# pc_healthypi_move_nRF5340_v2.net
KiCad netlist of a schematic drawn in EAGLE
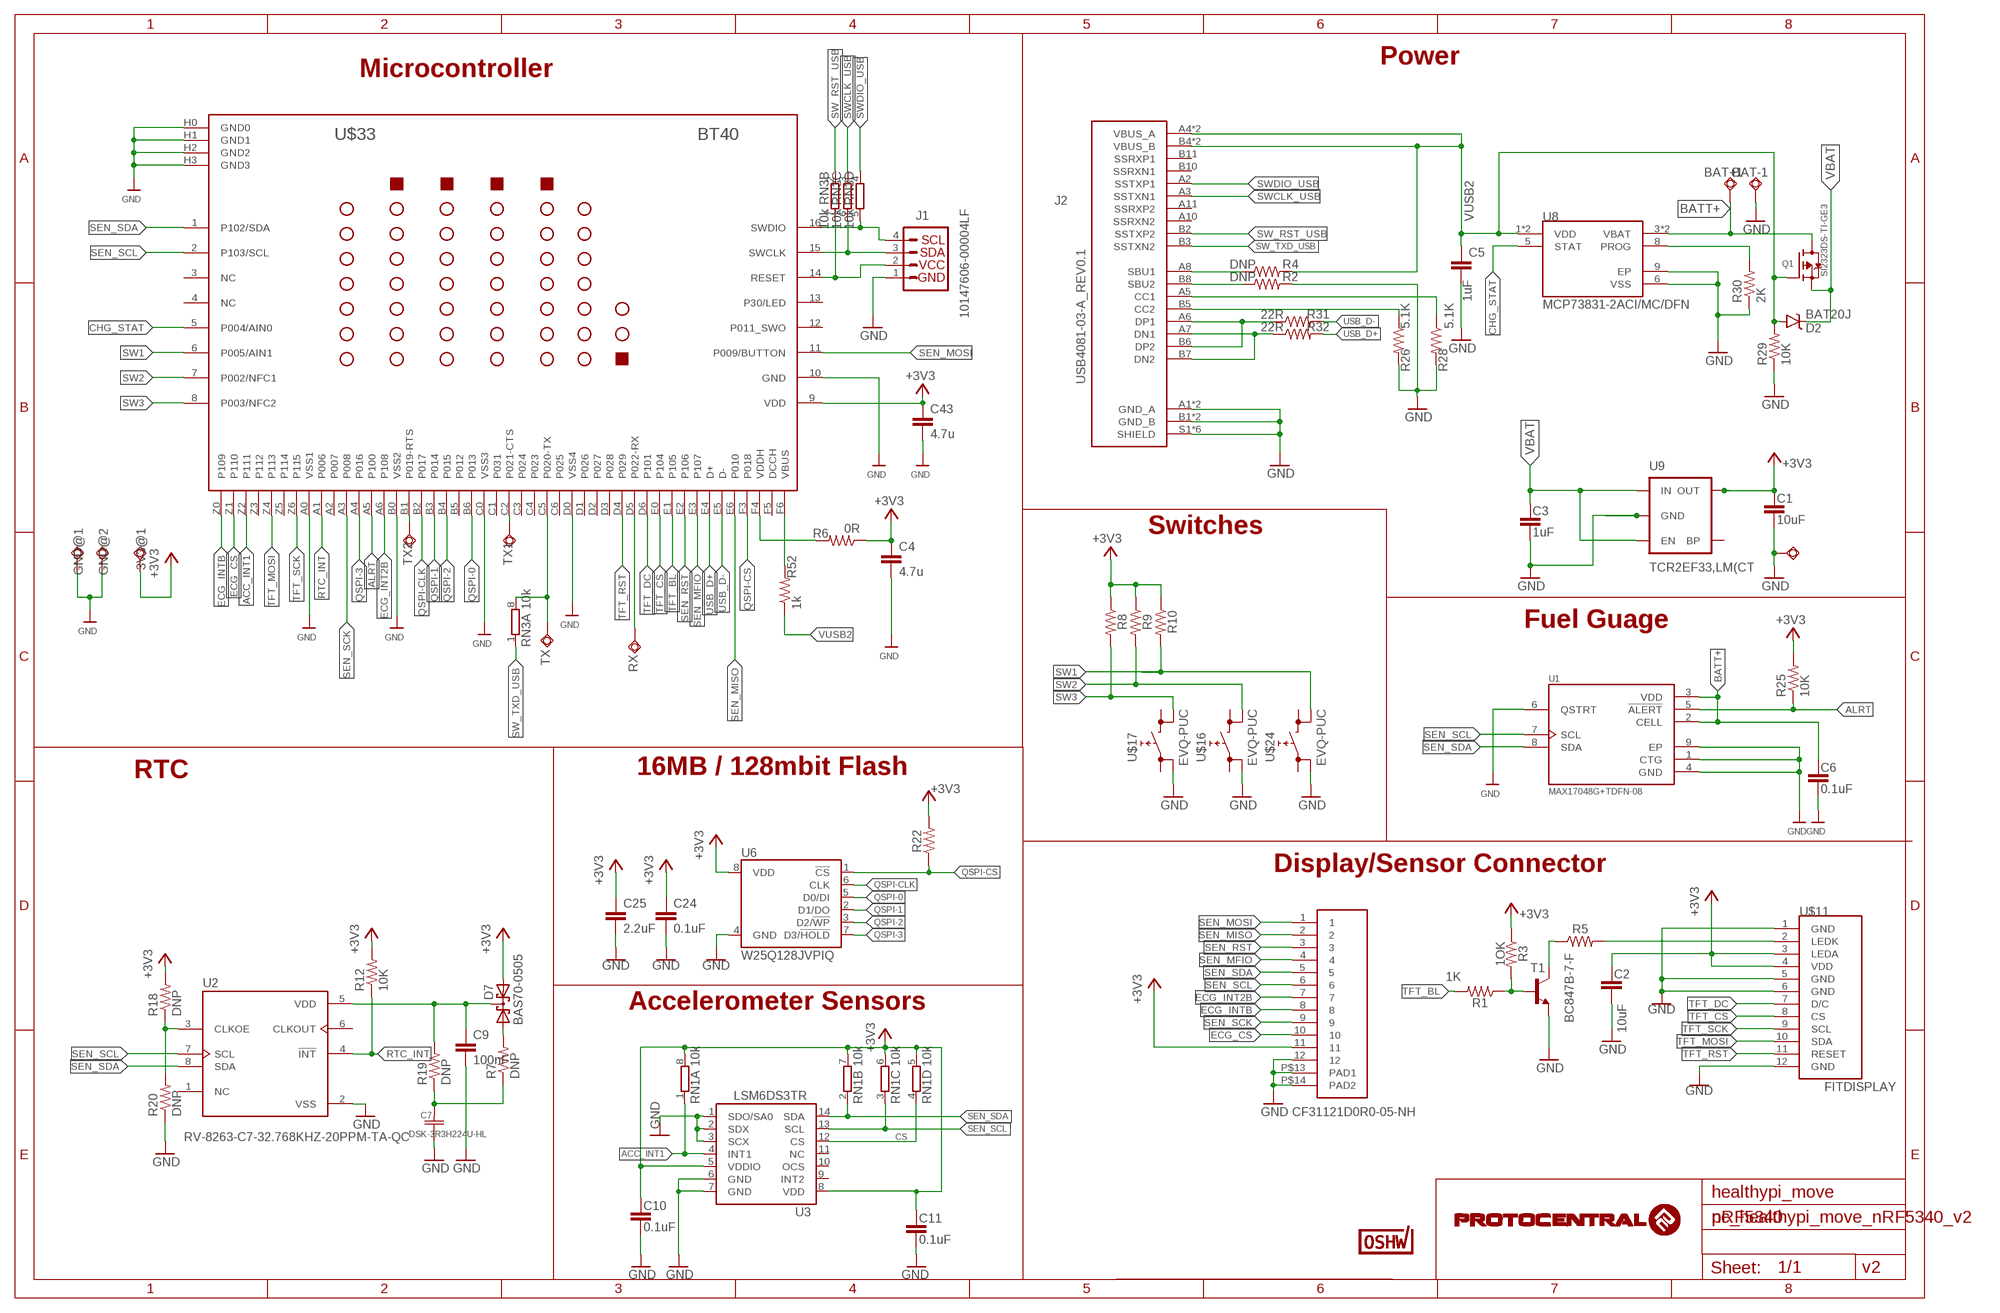
[diagram p0: schematic, sheet 1]

(export (version "E")
  (design (tool "Eeschema 10.0.6"))
  (components
    (comp (ref "3V3@1")
      (value "TPSQTP13SQ")
      (footprint "eagle-import:TP13SQ")
      (libsource (lib "eagle-import") (part "TPSQTP13SQ"))
    )
    (comp (ref "BAT+1")
      (value "TPSQTP13SQ")
      (footprint "eagle-import:TP13SQ")
      (libsource (lib "eagle-import") (part "TPSQTP13SQ"))
    )
    (comp (ref "BAT-1")
      (value "TPSQTP13SQ")
      (footprint "eagle-import:TP13SQ")
      (libsource (lib "eagle-import") (part "TPSQTP13SQ"))
    )
    (comp (ref "C1")
      (value "10uF")
      (footprint "eagle-import:0603@1")
      (libsource (lib "eagle-import") (part "0.1UF-0603-100V-10%"))
    )
    (comp (ref "C2")
      (value "10uF")
      (footprint "eagle-import:0603@1")
      (libsource (lib "eagle-import") (part "0.1UF-0603-100V-10%"))
    )
    (comp (ref "C3")
      (value "1uF")
      (footprint "eagle-import:0402-TIGHT")
      (libsource (lib "eagle-import") (part "0.1UF-0402T-6.3V-10%-X7R"))
    )
    (comp (ref "C4")
      (value "4.7u")
      (footprint "eagle-import:C0402")
      (libsource (lib "eagle-import") (part "C-EUC0402"))
    )
    (comp (ref "C5")
      (value "1uF")
      (footprint "eagle-import:0402-TIGHT")
      (libsource (lib "eagle-import") (part "2.2UF-0402_TIGHT-10V-10%-X5R"))
    )
    (comp (ref "C6")
      (value "0.1uF")
      (footprint "eagle-import:0402-TIGHT")
      (libsource (lib "eagle-import") (part "0.1UF-0402T-6.3V-10%-X7R"))
    )
    (comp (ref "C7")
      (value "DSK-3R3H224U-HL")
      (footprint "eagle-import:CAP_DSK-3R3H224U-HL_ELN")
      (fields (field (name "COPYRIGHT") "Copyright (C) 2023 Ultra Librarian. All rights reserved."))
      (libsource (lib "eagle-import") (part "DSK-3R3H224U-HL"))
    )
    (comp (ref "C9")
      (value "100nF")
      (footprint "eagle-import:C0402")
      (libsource (lib "eagle-import") (part "C-EUC0402"))
    )
    (comp (ref "C10")
      (value "0.1uF")
      (footprint "eagle-import:0402-TIGHT")
      (libsource (lib "eagle-import") (part "0.1UF-0402T-6.3V-10%-X7R"))
    )
    (comp (ref "C11")
      (value "0.1uF")
      (footprint "eagle-import:0402-TIGHT")
      (libsource (lib "eagle-import") (part "0.1UF-0402T-6.3V-10%-X7R"))
    )
    (comp (ref "C24")
      (value "0.1uF")
      (footprint "eagle-import:0402-TIGHT")
      (libsource (lib "eagle-import") (part "0.1UF-0402T-6.3V-10%-X7R"))
    )
    (comp (ref "C25")
      (value "2.2uF")
      (footprint "eagle-import:0402-TIGHT")
      (libsource (lib "eagle-import") (part "2.2UF-0402_TIGHT-10V-10%-X5R"))
    )
    (comp (ref "C43")
      (value "4.7u")
      (footprint "eagle-import:C0402")
      (libsource (lib "eagle-import") (part "C-EUC0402"))
    )
    (comp (ref "D2")
      (value "BAT20J")
      (footprint "eagle-import:SOD-323")
      (libsource (lib "eagle-import") (part "DIODE-SCHOTTKY-BAT20J"))
    )
    (comp (ref "D7")
      (value "BAS70-0505")
      (footprint "eagle-import:SOT23")
      (fields (field (name "MF") "Diotec") (field (name "MP") "BAS70-05"))
      (libsource (lib "eagle-import") (part "BAS70-0505"))
    )
    (comp (ref "GND@1")
      (value "TPSQTP13SQ")
      (footprint "eagle-import:TP13SQ")
      (libsource (lib "eagle-import") (part "TPSQTP13SQ"))
    )
    (comp (ref "GND@2")
      (value "TPSQTP13SQ")
      (footprint "eagle-import:TP13SQ")
      (libsource (lib "eagle-import") (part "TPSQTP13SQ"))
    )
    (comp (ref "J1")
      (value "10147606-00004LF")
      (footprint "eagle-import:JST04_1MM_RA")
      (libsource (lib "eagle-import") (part "QWIIC_CONNECTORJS-1MM"))
    )
    (comp (ref "J2")
      (value "USB4081-03-A_REV0.1")
      (footprint "eagle-import:GCT_USB4081-03-A_REV0.1")
      (fields (field (name "MF") "Global Connector Technology") (field (name "MP") "USB4081-03-A"))
      (libsource (lib "eagle-import") (part "USB4081-03-A_REV0.1"))
    )
    (comp (ref "Q1")
      (value "SI2323DS-TI-GE3")
      (footprint "eagle-import:SOT23-R")
      (libsource (lib "eagle-import") (part "MOSFET-P"))
    )
    (comp (ref "R1")
      (value "200")
      (footprint "eagle-import:R0402")
      (libsource (lib "eagle-import") (part "R-US_R0402"))
    )
    (comp (ref "R2")
      (value "DNP")
      (footprint "eagle-import:0402-RES")
      (libsource (lib "eagle-import") (part "RESISTOR0402-RES"))
    )
    (comp (ref "R3")
      (value "200")
      (footprint "eagle-import:R0402")
      (libsource (lib "eagle-import") (part "R-US_R0402"))
    )
    (comp (ref "R4")
      (value "DNP")
      (footprint "eagle-import:0402-RES")
      (libsource (lib "eagle-import") (part "RESISTOR0402-RES"))
    )
    (comp (ref "R5")
      (value "200R")
      (footprint "eagle-import:R0402")
      (libsource (lib "eagle-import") (part "R-US_R0402"))
    )
    (comp (ref "R6")
      (value "0R")
      (footprint "eagle-import:0402-RES")
      (libsource (lib "eagle-import") (part "RESISTOR0402-RES"))
    )
    (comp (ref "R7")
      (value "DNP")
      (footprint "eagle-import:R0402")
      (libsource (lib "eagle-import") (part "R-US_R0402"))
    )
    (comp (ref "R8")
      (value "200")
      (footprint "eagle-import:R0402")
      (libsource (lib "eagle-import") (part "R-US_R0402"))
    )
    (comp (ref "R9")
      (value "200")
      (footprint "eagle-import:R0402")
      (libsource (lib "eagle-import") (part "R-US_R0402"))
    )
    (comp (ref "R10")
      (value "200")
      (footprint "eagle-import:R0402")
      (libsource (lib "eagle-import") (part "R-US_R0402"))
    )
    (comp (ref "R12")
      (value "10K")
      (footprint "eagle-import:R0402")
      (libsource (lib "eagle-import") (part "R-US_R0402"))
    )
    (comp (ref "R18")
      (value "DNP")
      (footprint "eagle-import:R0402")
      (libsource (lib "eagle-import") (part "R-US_R0402"))
    )
    (comp (ref "R19")
      (value "DNP")
      (footprint "eagle-import:R0402")
      (libsource (lib "eagle-import") (part "R-US_R0402"))
    )
    (comp (ref "R20")
      (value "DNP")
      (footprint "eagle-import:R0402")
      (libsource (lib "eagle-import") (part "R-US_R0402"))
    )
    (comp (ref "R22")
      (value "10k")
      (footprint "eagle-import:R0402")
      (libsource (lib "eagle-import") (part "R-US_R0402"))
    )
    (comp (ref "R25")
      (value "10K")
      (footprint "eagle-import:0402-RES")
      (libsource (lib "eagle-import") (part "RESISTOR0402-RES"))
    )
    (comp (ref "R26")
      (value "5.1K")
      (footprint "eagle-import:0402-RES")
      (libsource (lib "eagle-import") (part "RESISTOR0402-RES"))
    )
    (comp (ref "R28")
      (value "5.1K")
      (footprint "eagle-import:0402-RES")
      (libsource (lib "eagle-import") (part "RESISTOR0402-RES"))
    )
    (comp (ref "R29")
      (value "10K")
      (footprint "eagle-import:R0402")
      (libsource (lib "eagle-import") (part "R-US_R0402"))
    )
    (comp (ref "R30")
      (value "2K")
      (footprint "eagle-import:R0402")
      (libsource (lib "eagle-import") (part "R-US_R0402"))
    )
    (comp (ref "R31")
      (value "22R")
      (footprint "eagle-import:0402-RES")
      (libsource (lib "eagle-import") (part "RESISTOR0402-RES"))
    )
    (comp (ref "R32")
      (value "22R")
      (footprint "eagle-import:0402-RES")
      (libsource (lib "eagle-import") (part "RESISTOR0402-RES"))
    )
    (comp (ref "R52")
      (value "1k")
      (footprint "eagle-import:0402-RES")
      (libsource (lib "eagle-import") (part "RESISTOR0402-RES"))
    )
    (comp (ref "RN1")
      (value "10k")
      (footprint "eagle-import:4X0402ARV341")
      (libsource (lib "eagle-import") (part "4R-N0402ARV341"))
    )
    (comp (ref "RN3")
      (value "10k")
      (footprint "eagle-import:4X0402ARV341")
      (libsource (lib "eagle-import") (part "4R-N0402ARV341"))
    )
    (comp (ref "RX")
      (value "TPSQTP13SQ")
      (footprint "eagle-import:TP13SQ")
      (libsource (lib "eagle-import") (part "TPSQTP13SQ"))
    )
    (comp (ref "SWIO6")
      (value "TPSQTP11R")
      (footprint "eagle-import:TP11R")
      (libsource (lib "eagle-import") (part "TPSQTP11R"))
    )
    (comp (ref "T1")
      (value "BC847B-7-F")
      (footprint "eagle-import:SOT23-BEC")
      (libsource (lib "eagle-import") (part "-NPN-SOT23-BECMMBT2222ALT1"))
    )
    (comp (ref "TX")
      (value "TPSQTP13SQ")
      (footprint "eagle-import:TP13SQ")
      (libsource (lib "eagle-import") (part "TPSQTP13SQ"))
    )
    (comp (ref "TX1")
      (value "TPSQTP13SQ")
      (footprint "eagle-import:TP13SQ")
      (libsource (lib "eagle-import") (part "TPSQTP13SQ"))
    )
    (comp (ref "TX2")
      (value "TPSQTP13SQ")
      (footprint "eagle-import:TP13SQ")
      (libsource (lib "eagle-import") (part "TPSQTP13SQ"))
    )
    (comp (ref "U$5")
      (value "CF31121D0R0-05-NH")
      (footprint "eagle-import:CF31121D0R0-05-NH")
      (libsource (lib "eagle-import") (part "CF31121D0R0-05-NH"))
    )
    (comp (ref "U$9")
      (value "CERT-SMALL")
      (footprint "eagle-import:CERT-SMALL-SILK")
      (libsource (lib "eagle-import") (part "CERT-SMALL"))
    )
    (comp (ref "U$11")
      (value "FITDISPLAY")
      (footprint "eagle-import:FITDISPLAY")
      (libsource (lib "eagle-import") (part "FITDISPLAY"))
    )
    (comp (ref "U$16")
      (value "EVQ-PUC")
      (footprint "eagle-import:EVQ-PUC")
      (libsource (lib "eagle-import") (part "EVQ-PUC"))
    )
    (comp (ref "U$17")
      (value "EVQ-PUC")
      (footprint "eagle-import:EVQ-PUC")
      (libsource (lib "eagle-import") (part "EVQ-PUC"))
    )
    (comp (ref "U$24")
      (value "EVQ-PUC")
      (footprint "eagle-import:EVQ-PUC")
      (libsource (lib "eagle-import") (part "EVQ-PUC"))
    )
    (comp (ref "U$33")
      (value "BT40")
      (footprint "eagle-import:BT40")
      (libsource (lib "eagle-import") (part "BT40"))
    )
    (comp (ref "U1")
      (value "MAX17048G+TDFN-08")
      (footprint "eagle-import:SON50P200X200X80-9N")
      (fields (field (name "MF") "Analog Devices") (field (name "MP") "MAX17048G+"))
      (libsource (lib "eagle-import") (part "MAX17048G+TDFN-08"))
    )
    (comp (ref "U2")
      (value "RV-8263-C7-32.768KHZ-20PPM-TA-QC")
      (footprint "eagle-import:IC_RV-8263-C7-32.768KHZ-20PPM-TA-QC")
      (fields (field (name "MF") "Micro Crystal"))
      (libsource (lib "eagle-import") (part "RV-8263-C7-32.768KHZ-20PPM-TA-QC"))
    )
    (comp (ref "U3")
      (value "LSM6DS3TR")
      (footprint "eagle-import:LGA14L")
      (libsource (lib "eagle-import") (part "LSM6DS3"))
    )
    (comp (ref "U6")
      (value "W25Q128JVPIQ")
      (footprint "eagle-import:WSON-8-6X5-SKINNY_CENTERPAD")
      (libsource (lib "eagle-import") (part "W25QXX128MBIT-6X5-SKINNY_CENTER"))
    )
    (comp (ref "U8")
      (value "MCP73831-2ACI/MC/DFN")
      (footprint "eagle-import:SON50P200X300X100-9N")
      (fields (field (name "MF") "Microchip Technology") (field (name "MP") "MCP73831-2ACI/MC"))
      (libsource (lib "eagle-import") (part "MCP73831-2ACI/MC/DFN"))
    )
    (comp (ref "U9")
      (value "TCR2EF33,LM(CT")
      (footprint "eagle-import:SOT23-5")
      (libsource (lib "eagle-import") (part "V_REG_LDOSMD"))
    )
  )
  (nets
    (net (code "1") (name "+3V3") (class "Default")
      (node (ref "3V3@1") (pin "TP") (pinfunction "TP_TP") (pintype "input"))
      (node (ref "C1") (pin "1") (pinfunction "1_1") (pintype "passive"))
      (node (ref "C10") (pin "1") (pinfunction "1_1") (pintype "passive"))
      (node (ref "C11") (pin "1") (pinfunction "1_1") (pintype "passive"))
      (node (ref "C2") (pin "1") (pinfunction "1_1") (pintype "passive"))
      (node (ref "C24") (pin "1") (pinfunction "1_1") (pintype "passive"))
      (node (ref "C25") (pin "1") (pinfunction "1_1") (pintype "passive"))
      (node (ref "C4") (pin "1") (pinfunction "1_1") (pintype "passive"))
      (node (ref "C43") (pin "1") (pinfunction "1_1") (pintype "passive"))
      (node (ref "D7") (pin "2") (pinfunction "A2_2") (pintype "passive"))
      (node (ref "R10") (pin "1") (pinfunction "1_1") (pintype "passive"))
      (node (ref "R12") (pin "2") (pinfunction "2_2") (pintype "passive"))
      (node (ref "R18") (pin "2") (pinfunction "2_2") (pintype "passive"))
      (node (ref "R22") (pin "2") (pinfunction "2_2") (pintype "passive"))
      (node (ref "R25") (pin "2") (pinfunction "2_2") (pintype "passive"))
      (node (ref "R3") (pin "1") (pinfunction "1_1") (pintype "passive"))
      (node (ref "R6") (pin "1") (pinfunction "1_1") (pintype "passive"))
      (node (ref "R8") (pin "1") (pinfunction "1_1") (pintype "passive"))
      (node (ref "R9") (pin "1") (pinfunction "1_1") (pintype "passive"))
      (node (ref "RN1") (pin "5") (pinfunction "2_5") (pintype "passive"))
      (node (ref "RN1") (pin "6") (pinfunction "2_6") (pintype "passive"))
      (node (ref "RN1") (pin "7") (pinfunction "2_7") (pintype "passive"))
      (node (ref "RN1") (pin "8") (pinfunction "2_8") (pintype "passive"))
      (node (ref "U$11") (pin "3") (pinfunction "LEDA_3") (pintype "bidirectional"))
      (node (ref "U$11") (pin "4") (pinfunction "VDD_4") (pintype "bidirectional"))
      (node (ref "U$33") (pin "9") (pinfunction "VDD_9") (pintype "bidirectional"))
      (node (ref "U$5") (pin "11") (pinfunction "11_11") (pintype "bidirectional"))
      (node (ref "U3") (pin "5") (pinfunction "VDDIO_5") (pintype "bidirectional"))
      (node (ref "U3") (pin "8") (pinfunction "VDD_8") (pintype "bidirectional"))
      (node (ref "U6") (pin "8") (pinfunction "VDD_8") (pintype "bidirectional"))
      (node (ref "U9") (pin "5") (pinfunction "OUT_5") (pintype "passive"))
    )
    (net (code "2") (name "/CS") (class "Default")
      (node (ref "RN1") (pin "4") (pinfunction "1_4") (pintype "passive"))
      (node (ref "U3") (pin "12") (pinfunction "CS_12") (pintype "bidirectional"))
    )
    (net (code "3") (name "ACC_INT1") (class "Default")
      (node (ref "RN1") (pin "1") (pinfunction "1_1") (pintype "passive"))
      (node (ref "U$33") (pin "Z2") (pinfunction "P111_Z2") (pintype "bidirectional"))
      (node (ref "U3") (pin "4") (pinfunction "INT1_4") (pintype "bidirectional"))
    )
    (net (code "4") (name "ALRT") (class "Default")
      (node (ref "R25") (pin "1") (pinfunction "1_1") (pintype "passive"))
      (node (ref "U$33") (pin "A5") (pinfunction "P100_A5") (pintype "bidirectional"))
      (node (ref "U1") (pin "5") (pinfunction "~{ALERT}_5") (pintype "output"))
    )
    (net (code "5") (name "BATT+") (class "Default")
      (node (ref "BAT+1") (pin "TP") (pinfunction "TP_TP") (pintype "input"))
      (node (ref "C6") (pin "1") (pinfunction "1_1") (pintype "passive"))
      (node (ref "Q1") (pin "3") (pinfunction "D_3") (pintype "passive"))
      (node (ref "U1") (pin "2") (pinfunction "CELL_2") (pintype "power_in"))
      (node (ref "U1") (pin "3") (pinfunction "VDD_3") (pintype "power_in"))
      (node (ref "U8") (pin "3") (pinfunction "VBAT_3") (pintype "output"))
      (node (ref "U8") (pin "4") (pinfunction "VBAT_4") (pintype "output"))
    )
    (net (code "6") (name "CHG_STAT") (class "Default")
      (node (ref "U$33") (pin "5") (pinfunction "P004/AIN0_5") (pintype "bidirectional"))
      (node (ref "U8") (pin "5") (pinfunction "STAT_5") (pintype "output"))
    )
    (net (code "7") (name "ECG_CS") (class "Default")
      (node (ref "U$33") (pin "Z1") (pinfunction "P110_Z1") (pintype "bidirectional"))
      (node (ref "U$5") (pin "10") (pinfunction "10_10") (pintype "bidirectional"))
    )
    (net (code "8") (name "ECG_INT2B") (class "Default")
      (node (ref "U$33") (pin "A6") (pinfunction "P108_A6") (pintype "bidirectional"))
      (node (ref "U$5") (pin "7") (pinfunction "7_7") (pintype "bidirectional"))
    )
    (net (code "9") (name "ECG_INTB") (class "Default")
      (node (ref "U$33") (pin "Z0") (pinfunction "P109_Z0") (pintype "bidirectional"))
      (node (ref "U$5") (pin "8") (pinfunction "8_8") (pintype "bidirectional"))
    )
    (net (code "10") (name "GND") (class "Default")
      (node (ref "BAT-1") (pin "TP") (pinfunction "TP_TP") (pintype "input"))
      (node (ref "C1") (pin "2") (pinfunction "2_2") (pintype "passive"))
      (node (ref "C10") (pin "2") (pinfunction "2_2") (pintype "passive"))
      (node (ref "C11") (pin "2") (pinfunction "2_2") (pintype "passive"))
      (node (ref "C2") (pin "2") (pinfunction "2_2") (pintype "passive"))
      (node (ref "C24") (pin "2") (pinfunction "2_2") (pintype "passive"))
      (node (ref "C25") (pin "2") (pinfunction "2_2") (pintype "passive"))
      (node (ref "C3") (pin "2") (pinfunction "2_2") (pintype "passive"))
      (node (ref "C4") (pin "2") (pinfunction "2_2") (pintype "passive"))
      (node (ref "C43") (pin "2") (pinfunction "2_2") (pintype "passive"))
      (node (ref "C5") (pin "2") (pinfunction "2_2") (pintype "passive"))
      (node (ref "C6") (pin "2") (pinfunction "2_2") (pintype "passive"))
      (node (ref "C7") (pin "1") (pinfunction "1_1") (pintype "passive"))
      (node (ref "C9") (pin "2") (pinfunction "2_2") (pintype "passive"))
      (node (ref "GND@1") (pin "TP") (pinfunction "TP_TP") (pintype "input"))
      (node (ref "GND@2") (pin "TP") (pinfunction "TP_TP") (pintype "input"))
      (node (ref "J1") (pin "1") (pinfunction "1_1") (pintype "power_in"))
      (node (ref "J2") (pin "A1") (pinfunction "GND_A_A1") (pintype "power_in"))
      (node (ref "J2") (pin "A12") (pinfunction "GND_A_A12") (pintype "power_in"))
      (node (ref "J2") (pin "B1") (pinfunction "GND_B_B1") (pintype "power_in"))
      (node (ref "J2") (pin "B12") (pinfunction "GND_B_B12") (pintype "power_in"))
      (node (ref "J2") (pin "S1") (pinfunction "SHIELD_S1") (pintype "passive"))
      (node (ref "J2") (pin "S2") (pinfunction "SHIELD_S2") (pintype "passive"))
      (node (ref "J2") (pin "S3") (pinfunction "SHIELD_S3") (pintype "passive"))
      (node (ref "J2") (pin "S4") (pinfunction "SHIELD_S4") (pintype "passive"))
      (node (ref "J2") (pin "S5") (pinfunction "SHIELD_S5") (pintype "passive"))
      (node (ref "J2") (pin "S6") (pinfunction "SHIELD_S6") (pintype "passive"))
      (node (ref "R2") (pin "2") (pinfunction "2_2") (pintype "passive"))
      (node (ref "R20") (pin "1") (pinfunction "1_1") (pintype "passive"))
      (node (ref "R26") (pin "2") (pinfunction "2_2") (pintype "passive"))
      (node (ref "R28") (pin "2") (pinfunction "2_2") (pintype "passive"))
      (node (ref "R29") (pin "1") (pinfunction "1_1") (pintype "passive"))
      (node (ref "R30") (pin "1") (pinfunction "1_1") (pintype "passive"))
      (node (ref "SWIO6") (pin "TP") (pinfunction "TP_TP") (pintype "input"))
      (node (ref "T1") (pin "E") (pinfunction "E_E") (pintype "passive"))
      (node (ref "U$11") (pin "1") (pinfunction "GND_1") (pintype "bidirectional"))
      (node (ref "U$11") (pin "12") (pinfunction "GND_12") (pintype "bidirectional"))
      (node (ref "U$11") (pin "5") (pinfunction "GND_5") (pintype "bidirectional"))
      (node (ref "U$11") (pin "6") (pinfunction "GND_6") (pintype "bidirectional"))
      (node (ref "U$16") (pin "3") (pinfunction "0_3") (pintype "passive"))
      (node (ref "U$17") (pin "3") (pinfunction "0_3") (pintype "passive"))
      (node (ref "U$24") (pin "3") (pinfunction "0_3") (pintype "passive"))
      (node (ref "U$33") (pin "10") (pinfunction "GND_10") (pintype "bidirectional"))
      (node (ref "U$33") (pin "A0") (pinfunction "VSS1_A0") (pintype "bidirectional"))
      (node (ref "U$33") (pin "B0") (pinfunction "VSS2_B0") (pintype "bidirectional"))
      (node (ref "U$33") (pin "C0") (pinfunction "VSS3_C0") (pintype "bidirectional"))
      (node (ref "U$33") (pin "D0") (pinfunction "VSS4_D0") (pintype "bidirectional"))
      (node (ref "U$33") (pin "H0") (pinfunction "GND0_H0") (pintype "bidirectional"))
      (node (ref "U$33") (pin "H1") (pinfunction "GND1_H1") (pintype "bidirectional"))
      (node (ref "U$33") (pin "H2") (pinfunction "GND2_H2") (pintype "bidirectional"))
      (node (ref "U$33") (pin "H3") (pinfunction "GND3_H3") (pintype "bidirectional"))
      (node (ref "U$5") (pin "12") (pinfunction "12_12") (pintype "bidirectional"))
      (node (ref "U$5") (pin "P$13") (pinfunction "PAD1_P$13") (pintype "bidirectional"))
      (node (ref "U$5") (pin "P$14") (pinfunction "PAD2_P$14") (pintype "bidirectional"))
      (node (ref "U1") (pin "1") (pinfunction "CTG_1") (pintype "power_in"))
      (node (ref "U1") (pin "4") (pinfunction "GND_4") (pintype "power_in"))
      (node (ref "U1") (pin "6") (pinfunction "QSTRT_6") (pintype "input"))
      (node (ref "U1") (pin "9") (pinfunction "EP_9") (pintype "power_in"))
      (node (ref "U2") (pin "2") (pinfunction "VSS_2") (pintype "power_in"))
      (node (ref "U3") (pin "1") (pinfunction "SDO/SA0_1") (pintype "bidirectional"))
      (node (ref "U3") (pin "2") (pinfunction "SDX_2") (pintype "bidirectional"))
      (node (ref "U3") (pin "3") (pinfunction "SCX_3") (pintype "bidirectional"))
      (node (ref "U3") (pin "6") (pinfunction "GND_6") (pintype "bidirectional"))
      (node (ref "U3") (pin "7") (pinfunction "GND_7") (pintype "bidirectional"))
      (node (ref "U6") (pin "4") (pinfunction "GND_4") (pintype "bidirectional"))
      (node (ref "U8") (pin "6") (pinfunction "VSS_6") (pintype "power_in"))
      (node (ref "U8") (pin "9") (pinfunction "EP_9") (pintype "power_in"))
      (node (ref "U9") (pin "2") (pinfunction "GND_2") (pintype "input"))
    )
    (net (code "11") (name "Net-(C7-Pad2)") (class "Default")
      (node (ref "C7") (pin "2") (pinfunction "2_2") (pintype "passive"))
      (node (ref "R19") (pin "1") (pinfunction "1_1") (pintype "passive"))
      (node (ref "R7") (pin "1") (pinfunction "1_1") (pintype "passive"))
    )
    (net (code "12") (name "Net-(D7-A1)") (class "Default")
      (node (ref "D7") (pin "1") (pinfunction "A1_1") (pintype "passive"))
      (node (ref "R7") (pin "2") (pinfunction "2_2") (pintype "passive"))
    )
    (net (code "13") (name "Net-(D7-K1K2)") (class "Default")
      (node (ref "C9") (pin "1") (pinfunction "1_1") (pintype "passive"))
      (node (ref "D7") (pin "3") (pinfunction "K1K2_3") (pintype "passive"))
      (node (ref "R19") (pin "2") (pinfunction "2_2") (pintype "passive"))
      (node (ref "U2") (pin "5") (pinfunction "VDD_5") (pintype "power_in"))
    )
    (net (code "14") (name "Net-(J2-CC1)") (class "Default")
      (node (ref "J2") (pin "A5") (pinfunction "CC1_A5") (pintype "bidirectional"))
      (node (ref "R28") (pin "1") (pinfunction "1_1") (pintype "passive"))
    )
    (net (code "15") (name "Net-(J2-CC2)") (class "Default")
      (node (ref "J2") (pin "B5") (pinfunction "CC2_B5") (pintype "bidirectional"))
      (node (ref "R26") (pin "1") (pinfunction "1_1") (pintype "passive"))
    )
    (net (code "16") (name "Net-(J2-DN1)") (class "Default")
      (node (ref "J2") (pin "A7") (pinfunction "DN1_A7") (pintype "bidirectional"))
      (node (ref "J2") (pin "B7") (pinfunction "DN2_B7") (pintype "bidirectional"))
      (node (ref "R32") (pin "1") (pinfunction "1_1") (pintype "passive"))
    )
    (net (code "17") (name "Net-(J2-DP1)") (class "Default")
      (node (ref "J2") (pin "A6") (pinfunction "DP1_A6") (pintype "bidirectional"))
      (node (ref "J2") (pin "B6") (pinfunction "DP2_B6") (pintype "bidirectional"))
      (node (ref "R31") (pin "1") (pinfunction "1_1") (pintype "passive"))
    )
    (net (code "18") (name "Net-(J2-SBU1)") (class "Default")
      (node (ref "J2") (pin "A8") (pinfunction "SBU1_A8") (pintype "bidirectional"))
      (node (ref "R4") (pin "1") (pinfunction "1_1") (pintype "passive"))
    )
    (net (code "19") (name "Net-(J2-SBU2)") (class "Default")
      (node (ref "J2") (pin "B8") (pinfunction "SBU2_B8") (pintype "bidirectional"))
      (node (ref "R2") (pin "1") (pinfunction "1_1") (pintype "passive"))
    )
    (net (code "20") (name "Net-(R1-Pad1)") (class "Default")
      (node (ref "R1") (pin "1") (pinfunction "1_1") (pintype "passive"))
      (node (ref "R3") (pin "2") (pinfunction "2_2") (pintype "passive"))
      (node (ref "T1") (pin "B") (pinfunction "B_B") (pintype "passive"))
    )
    (net (code "21") (name "Net-(R5-Pad1)") (class "Default")
      (node (ref "R5") (pin "1") (pinfunction "1_1") (pintype "passive"))
      (node (ref "T1") (pin "C") (pinfunction "C_C") (pintype "passive"))
    )
    (net (code "22") (name "Net-(RN3A-2)") (class "Default")
      (node (ref "RN3") (pin "8") (pinfunction "2_8") (pintype "passive"))
      (node (ref "TX") (pin "TP") (pinfunction "TP_TP") (pintype "input"))
      (node (ref "U$33") (pin "C5") (pinfunction "P020-TX_C5") (pintype "bidirectional"))
    )
    (net (code "23") (name "Net-(RN3B-2)") (class "Default")
      (node (ref "J1") (pin "2") (pinfunction "2_2") (pintype "power_in"))
      (node (ref "RN3") (pin "7") (pinfunction "2_7") (pintype "passive"))
      (node (ref "U$33") (pin "14") (pinfunction "RESET_14") (pintype "bidirectional"))
    )
    (net (code "24") (name "Net-(RN3C-2)") (class "Default")
      (node (ref "J1") (pin "3") (pinfunction "3_3") (pintype "passive"))
      (node (ref "RN3") (pin "6") (pinfunction "2_6") (pintype "passive"))
      (node (ref "U$33") (pin "15") (pinfunction "SWCLK_15") (pintype "bidirectional"))
    )
    (net (code "25") (name "Net-(RN3D-2)") (class "Default")
      (node (ref "J1") (pin "4") (pinfunction "4_4") (pintype "passive"))
      (node (ref "RN3") (pin "5") (pinfunction "2_5") (pintype "passive"))
      (node (ref "U$33") (pin "16") (pinfunction "SWDIO_16") (pintype "bidirectional"))
    )
    (net (code "26") (name "Net-(U$11-LEDK)") (class "Default")
      (node (ref "R5") (pin "2") (pinfunction "2_2") (pintype "passive"))
      (node (ref "U$11") (pin "2") (pinfunction "LEDK_2") (pintype "bidirectional"))
    )
    (net (code "27") (name "Net-(U$33-P019-RTS)") (class "Default")
      (node (ref "TX2") (pin "TP") (pinfunction "TP_TP") (pintype "input"))
      (node (ref "U$33") (pin "B1") (pinfunction "P019-RTS_B1") (pintype "bidirectional"))
    )
    (net (code "28") (name "Net-(U$33-P021-CTS)") (class "Default")
      (node (ref "TX1") (pin "TP") (pinfunction "TP_TP") (pintype "input"))
      (node (ref "U$33") (pin "C2") (pinfunction "P021-CTS_C2") (pintype "bidirectional"))
    )
    (net (code "29") (name "Net-(U$33-P022-RX)") (class "Default")
      (node (ref "RX") (pin "TP") (pinfunction "TP_TP") (pintype "input"))
      (node (ref "U$33") (pin "D5") (pinfunction "P022-RX_D5") (pintype "bidirectional"))
    )
    (net (code "30") (name "Net-(U$33-VBUS)") (class "Default")
      (node (ref "R52") (pin "2") (pinfunction "2_2") (pintype "passive"))
      (node (ref "U$33") (pin "F6") (pinfunction "VBUS_F6") (pintype "bidirectional"))
    )
    (net (code "31") (name "Net-(U$33-VDDH)") (class "Default")
      (node (ref "R6") (pin "2") (pinfunction "2_2") (pintype "passive"))
      (node (ref "U$33") (pin "F4") (pinfunction "VDDH_F4") (pintype "bidirectional"))
    )
    (net (code "32") (name "Net-(U2-CLKOE)") (class "Default")
      (node (ref "R18") (pin "1") (pinfunction "1_1") (pintype "passive"))
      (node (ref "R20") (pin "2") (pinfunction "2_2") (pintype "passive"))
      (node (ref "U2") (pin "3") (pinfunction "CLKOE_3") (pintype "input"))
    )
    (net (code "33") (name "Net-(U8-PROG)") (class "Default")
      (node (ref "R30") (pin "2") (pinfunction "2_2") (pintype "passive"))
      (node (ref "U8") (pin "8") (pinfunction "PROG_8") (pintype "input"))
    )
    (net (code "34") (name "QSPI-0") (class "Default")
      (node (ref "U$33") (pin "B6") (pinfunction "P013_B6") (pintype "bidirectional"))
      (node (ref "U6") (pin "5") (pinfunction "D0/DI_5") (pintype "bidirectional"))
    )
    (net (code "35") (name "QSPI-1") (class "Default")
      (node (ref "U$33") (pin "B3") (pinfunction "P014_B3") (pintype "bidirectional"))
      (node (ref "U6") (pin "2") (pinfunction "D1/DO_2") (pintype "bidirectional"))
    )
    (net (code "36") (name "QSPI-2") (class "Default")
      (node (ref "U$33") (pin "B4") (pinfunction "P015_B4") (pintype "bidirectional"))
      (node (ref "U6") (pin "3") (pinfunction "D2/~{WP}_3") (pintype "bidirectional"))
    )
    (net (code "37") (name "QSPI-3") (class "Default")
      (node (ref "U$33") (pin "A4") (pinfunction "P016_A4") (pintype "bidirectional"))
      (node (ref "U6") (pin "7") (pinfunction "D3/~{HOLD}_7") (pintype "bidirectional"))
    )
    (net (code "38") (name "QSPI-CLK") (class "Default")
      (node (ref "U$33") (pin "B2") (pinfunction "P017_B2") (pintype "bidirectional"))
      (node (ref "U6") (pin "6") (pinfunction "CLK_6") (pintype "bidirectional"))
    )
    (net (code "39") (name "QSPI-CS") (class "Default")
      (node (ref "R22") (pin "1") (pinfunction "1_1") (pintype "passive"))
      (node (ref "U$33") (pin "F3") (pinfunction "P018_F3") (pintype "bidirectional"))
      (node (ref "U6") (pin "1") (pinfunction "~{CS}_1") (pintype "bidirectional"))
    )
    (net (code "40") (name "RTC_INT") (class "Default")
      (node (ref "R12") (pin "1") (pinfunction "1_1") (pintype "passive"))
      (node (ref "U$33") (pin "A1") (pinfunction "P006_A1") (pintype "bidirectional"))
      (node (ref "U2") (pin "4") (pinfunction "~{INT}_4") (pintype "output"))
    )
    (net (code "41") (name "SEN_MFIO") (class "Default")
      (node (ref "U$33") (pin "E3") (pinfunction "P107_E3") (pintype "bidirectional"))
      (node (ref "U$5") (pin "4") (pinfunction "4_4") (pintype "bidirectional"))
    )
    (net (code "42") (name "SEN_MISO") (class "Default")
      (node (ref "U$33") (pin "E6") (pinfunction "P010_E6") (pintype "bidirectional"))
      (node (ref "U$5") (pin "2") (pinfunction "2_2") (pintype "bidirectional"))
    )
    (net (code "43") (name "SEN_MOSI") (class "Default")
      (node (ref "U$33") (pin "11") (pinfunction "P009/BUTTON_11") (pintype "bidirectional"))
      (node (ref "U$5") (pin "1") (pinfunction "1_1") (pintype "bidirectional"))
    )
    (net (code "44") (name "SEN_RST") (class "Default")
      (node (ref "U$33") (pin "E2") (pinfunction "P106_E2") (pintype "bidirectional"))
      (node (ref "U$5") (pin "3") (pinfunction "3_3") (pintype "bidirectional"))
    )
    (net (code "45") (name "SEN_SCK") (class "Default")
      (node (ref "U$33") (pin "A3") (pinfunction "P008_A3") (pintype "bidirectional"))
      (node (ref "U$5") (pin "9") (pinfunction "9_9") (pintype "bidirectional"))
    )
    (net (code "46") (name "SEN_SCL") (class "Default")
      (node (ref "RN1") (pin "3") (pinfunction "1_3") (pintype "passive"))
      (node (ref "U$33") (pin "2") (pinfunction "P103/SCL_2") (pintype "bidirectional"))
      (node (ref "U$5") (pin "6") (pinfunction "6_6") (pintype "bidirectional"))
      (node (ref "U1") (pin "7") (pinfunction "SCL_7") (pintype "input"))
      (node (ref "U2") (pin "7") (pinfunction "SCL_7") (pintype "input"))
      (node (ref "U3") (pin "13") (pinfunction "SCL_13") (pintype "bidirectional"))
    )
    (net (code "47") (name "SEN_SDA") (class "Default")
      (node (ref "RN1") (pin "2") (pinfunction "1_2") (pintype "passive"))
      (node (ref "U$33") (pin "1") (pinfunction "P102/SDA_1") (pintype "bidirectional"))
      (node (ref "U$5") (pin "5") (pinfunction "5_5") (pintype "bidirectional"))
      (node (ref "U1") (pin "8") (pinfunction "SDA_8") (pintype "bidirectional"))
      (node (ref "U2") (pin "8") (pinfunction "SDA_8") (pintype "bidirectional"))
      (node (ref "U3") (pin "14") (pinfunction "SDA_14") (pintype "bidirectional"))
    )
    (net (code "48") (name "SW1") (class "Default")
      (node (ref "R10") (pin "2") (pinfunction "2_2") (pintype "passive"))
      (node (ref "U$24") (pin "2") (pinfunction "1_2") (pintype "passive"))
      (node (ref "U$33") (pin "6") (pinfunction "P005/AIN1_6") (pintype "bidirectional"))
    )
    (net (code "49") (name "SW2") (class "Default")
      (node (ref "R9") (pin "2") (pinfunction "2_2") (pintype "passive"))
      (node (ref "U$16") (pin "2") (pinfunction "1_2") (pintype "passive"))
      (node (ref "U$33") (pin "7") (pinfunction "P002/NFC1_7") (pintype "bidirectional"))
    )
    (net (code "50") (name "SW3") (class "Default")
      (node (ref "R8") (pin "2") (pinfunction "2_2") (pintype "passive"))
      (node (ref "U$17") (pin "2") (pinfunction "1_2") (pintype "passive"))
      (node (ref "U$33") (pin "8") (pinfunction "P003/NFC2_8") (pintype "bidirectional"))
    )
    (net (code "51") (name "SWCLK_USB") (class "Default")
      (node (ref "J2") (pin "A3") (pinfunction "SSTXN1_A3") (pintype "bidirectional"))
      (node (ref "RN3") (pin "3") (pinfunction "1_3") (pintype "passive"))
    )
    (net (code "52") (name "SWDIO_USB") (class "Default")
      (node (ref "J2") (pin "A2") (pinfunction "SSTXP1_A2") (pintype "bidirectional"))
      (node (ref "RN3") (pin "4") (pinfunction "1_4") (pintype "passive"))
    )
    (net (code "53") (name "SW_RST_USB") (class "Default")
      (node (ref "J2") (pin "B2") (pinfunction "SSTXP2_B2") (pintype "bidirectional"))
      (node (ref "RN3") (pin "2") (pinfunction "1_2") (pintype "passive"))
    )
    (net (code "54") (name "SW_TXD_USB") (class "Default")
      (node (ref "J2") (pin "B3") (pinfunction "SSTXN2_B3") (pintype "bidirectional"))
      (node (ref "RN3") (pin "1") (pinfunction "1_1") (pintype "passive"))
    )
    (net (code "55") (name "TFT_BL") (class "Default")
      (node (ref "R1") (pin "2") (pinfunction "2_2") (pintype "passive"))
      (node (ref "U$33") (pin "E1") (pinfunction "P105_E1") (pintype "bidirectional"))
    )
    (net (code "56") (name "TFT_CS") (class "Default")
      (node (ref "U$11") (pin "8") (pinfunction "CS_8") (pintype "bidirectional"))
      (node (ref "U$33") (pin "E0") (pinfunction "P104_E0") (pintype "bidirectional"))
    )
    (net (code "57") (name "TFT_DC") (class "Default")
      (node (ref "U$11") (pin "7") (pinfunction "D/C_7") (pintype "bidirectional"))
      (node (ref "U$33") (pin "D6") (pinfunction "P101_D6") (pintype "bidirectional"))
    )
    (net (code "58") (name "TFT_MOSI") (class "Default")
      (node (ref "U$11") (pin "10") (pinfunction "SDA_10") (pintype "bidirectional"))
      (node (ref "U$33") (pin "Z4") (pinfunction "P113_Z4") (pintype "bidirectional"))
    )
    (net (code "59") (name "TFT_RST") (class "Default")
      (node (ref "U$11") (pin "11") (pinfunction "RESET_11") (pintype "bidirectional"))
      (node (ref "U$33") (pin "D4") (pinfunction "P029_D4") (pintype "bidirectional"))
    )
    (net (code "60") (name "TFT_SCK") (class "Default")
      (node (ref "U$11") (pin "9") (pinfunction "SCL_9") (pintype "bidirectional"))
      (node (ref "U$33") (pin "Z6") (pinfunction "P115_Z6") (pintype "bidirectional"))
    )
    (net (code "61") (name "USB_D+") (class "Default")
      (node (ref "R32") (pin "2") (pinfunction "2_2") (pintype "passive"))
      (node (ref "U$33") (pin "E4") (pinfunction "D+_E4") (pintype "bidirectional"))
    )
    (net (code "62") (name "USB_D-") (class "Default")
      (node (ref "R31") (pin "2") (pinfunction "2_2") (pintype "passive"))
      (node (ref "U$33") (pin "E5") (pinfunction "D-_E5") (pintype "bidirectional"))
    )
    (net (code "63") (name "VBAT") (class "Default")
      (node (ref "C3") (pin "1") (pinfunction "1_1") (pintype "passive"))
      (node (ref "D2") (pin "C") (pinfunction "C_C") (pintype "passive"))
      (node (ref "Q1") (pin "2") (pinfunction "S_2") (pintype "passive"))
      (node (ref "U9") (pin "1") (pinfunction "IN_1") (pintype "input"))
      (node (ref "U9") (pin "3") (pinfunction "EN_3") (pintype "input"))
    )
    (net (code "64") (name "VUSB2") (class "Default")
      (node (ref "C5") (pin "1") (pinfunction "1_1") (pintype "passive"))
      (node (ref "D2") (pin "A") (pinfunction "A_A") (pintype "passive"))
      (node (ref "J2") (pin "A4") (pinfunction "VBUS_A_A4") (pintype "power_in"))
      (node (ref "J2") (pin "A9") (pinfunction "VBUS_A_A9") (pintype "power_in"))
      (node (ref "J2") (pin "B4") (pinfunction "VBUS_B_B4") (pintype "power_in"))
      (node (ref "J2") (pin "B9") (pinfunction "VBUS_B_B9") (pintype "power_in"))
      (node (ref "Q1") (pin "1") (pinfunction "G_1") (pintype "passive"))
      (node (ref "R29") (pin "2") (pinfunction "2_2") (pintype "passive"))
      (node (ref "R4") (pin "2") (pinfunction "2_2") (pintype "passive"))
      (node (ref "R52") (pin "1") (pinfunction "1_1") (pintype "passive"))
      (node (ref "U8") (pin "1") (pinfunction "VDD_1") (pintype "power_in"))
      (node (ref "U8") (pin "2") (pinfunction "VDD_2") (pintype "power_in"))
    )
    (net (code "65") (name "unconnected-(J2-SSRXN1-PadB10)") (class "Default")
      (node (ref "J2") (pin "B10") (pinfunction "SSRXN1_B10") (pintype "bidirectional"))
    )
    (net (code "66") (name "unconnected-(J2-SSRXN2-PadA10)") (class "Default")
      (node (ref "J2") (pin "A10") (pinfunction "SSRXN2_A10") (pintype "bidirectional"))
    )
    (net (code "67") (name "unconnected-(J2-SSRXP1-PadB11)") (class "Default")
      (node (ref "J2") (pin "B11") (pinfunction "SSRXP1_B11") (pintype "bidirectional"))
    )
    (net (code "68") (name "unconnected-(J2-SSRXP2-PadA11)") (class "Default")
      (node (ref "J2") (pin "A11") (pinfunction "SSRXP2_A11") (pintype "bidirectional"))
    )
    (net (code "69") (name "unconnected-(U$16-0-Pad1)") (class "Default")
      (node (ref "U$16") (pin "1") (pinfunction "0_1") (pintype "passive"))
    )
    (net (code "70") (name "unconnected-(U$16-1-Pad4)") (class "Default")
      (node (ref "U$16") (pin "4") (pinfunction "1_4") (pintype "passive"))
    )
    (net (code "71") (name "unconnected-(U$17-0-Pad1)") (class "Default")
      (node (ref "U$17") (pin "1") (pinfunction "0_1") (pintype "passive"))
    )
    (net (code "72") (name "unconnected-(U$17-1-Pad4)") (class "Default")
      (node (ref "U$17") (pin "4") (pinfunction "1_4") (pintype "passive"))
    )
    (net (code "73") (name "unconnected-(U$24-0-Pad1)") (class "Default")
      (node (ref "U$24") (pin "1") (pinfunction "0_1") (pintype "passive"))
    )
    (net (code "74") (name "unconnected-(U$24-1-Pad4)") (class "Default")
      (node (ref "U$24") (pin "4") (pinfunction "1_4") (pintype "passive"))
    )
    (net (code "75") (name "unconnected-(U$33-DCCH-PadF5)") (class "Default")
      (node (ref "U$33") (pin "F5") (pinfunction "DCCH_F5") (pintype "bidirectional"))
    )
    (net (code "76") (name "unconnected-(U$33-NC-Pad3)") (class "Default")
      (node (ref "U$33") (pin "3") (pinfunction "NC_3") (pintype "bidirectional"))
    )
    (net (code "77") (name "unconnected-(U$33-NC-Pad4)") (class "Default")
      (node (ref "U$33") (pin "4") (pinfunction "NC_4") (pintype "bidirectional"))
    )
    (net (code "78") (name "unconnected-(U$33-P007-PadA2)") (class "Default")
      (node (ref "U$33") (pin "A2") (pinfunction "P007_A2") (pintype "bidirectional"))
    )
    (net (code "79") (name "unconnected-(U$33-P011_SWO-Pad12)") (class "Default")
      (node (ref "U$33") (pin "12") (pinfunction "P011_SWO_12") (pintype "bidirectional"))
    )
    (net (code "80") (name "unconnected-(U$33-P012-PadB5)") (class "Default")
      (node (ref "U$33") (pin "B5") (pinfunction "P012_B5") (pintype "bidirectional"))
    )
    (net (code "81") (name "unconnected-(U$33-P023-PadC4)") (class "Default")
      (node (ref "U$33") (pin "C4") (pinfunction "P023_C4") (pintype "bidirectional"))
    )
    (net (code "82") (name "unconnected-(U$33-P024-PadC3)") (class "Default")
      (node (ref "U$33") (pin "C3") (pinfunction "P024_C3") (pintype "bidirectional"))
    )
    (net (code "83") (name "unconnected-(U$33-P025-PadC6)") (class "Default")
      (node (ref "U$33") (pin "C6") (pinfunction "P025_C6") (pintype "bidirectional"))
    )
    (net (code "84") (name "unconnected-(U$33-P026-PadD1)") (class "Default")
      (node (ref "U$33") (pin "D1") (pinfunction "P026_D1") (pintype "bidirectional"))
    )
    (net (code "85") (name "unconnected-(U$33-P027-PadD2)") (class "Default")
      (node (ref "U$33") (pin "D2") (pinfunction "P027_D2") (pintype "bidirectional"))
    )
    (net (code "86") (name "unconnected-(U$33-P028-PadD3)") (class "Default")
      (node (ref "U$33") (pin "D3") (pinfunction "P028_D3") (pintype "bidirectional"))
    )
    (net (code "87") (name "unconnected-(U$33-P30{slash}LED-Pad13)") (class "Default")
      (node (ref "U$33") (pin "13") (pinfunction "P30/LED_13") (pintype "bidirectional"))
    )
    (net (code "88") (name "unconnected-(U$33-P031-PadC1)") (class "Default")
      (node (ref "U$33") (pin "C1") (pinfunction "P031_C1") (pintype "bidirectional"))
    )
    (net (code "89") (name "unconnected-(U$33-P112-PadZ3)") (class "Default")
      (node (ref "U$33") (pin "Z3") (pinfunction "P112_Z3") (pintype "bidirectional"))
    )
    (net (code "90") (name "unconnected-(U$33-P114-PadZ5)") (class "Default")
      (node (ref "U$33") (pin "Z5") (pinfunction "P114_Z5") (pintype "bidirectional"))
    )
    (net (code "91") (name "unconnected-(U2-CLKOUT-Pad6)") (class "Default")
      (node (ref "U2") (pin "6") (pinfunction "CLKOUT_6") (pintype "output"))
    )
    (net (code "92") (name "unconnected-(U2-NC-Pad1)") (class "Default")
      (node (ref "U2") (pin "1") (pinfunction "NC_1") (pintype "no_connect"))
    )
    (net (code "93") (name "unconnected-(U3-INT2-Pad9)") (class "Default")
      (node (ref "U3") (pin "9") (pinfunction "INT2_9") (pintype "bidirectional"))
    )
    (net (code "94") (name "unconnected-(U3-NC-Pad11)") (class "Default")
      (node (ref "U3") (pin "11") (pinfunction "NC_11") (pintype "bidirectional"))
    )
    (net (code "95") (name "unconnected-(U3-OCS-Pad10)") (class "Default")
      (node (ref "U3") (pin "10") (pinfunction "OCS_10") (pintype "bidirectional"))
    )
    (net (code "96") (name "unconnected-(U9-BP-Pad4)") (class "Default")
      (node (ref "U9") (pin "4") (pinfunction "BP_4") (pintype "input"))
    )
  )
)
